# Input_Board.net
KiCad netlist of a schematic drawn in EAGLE
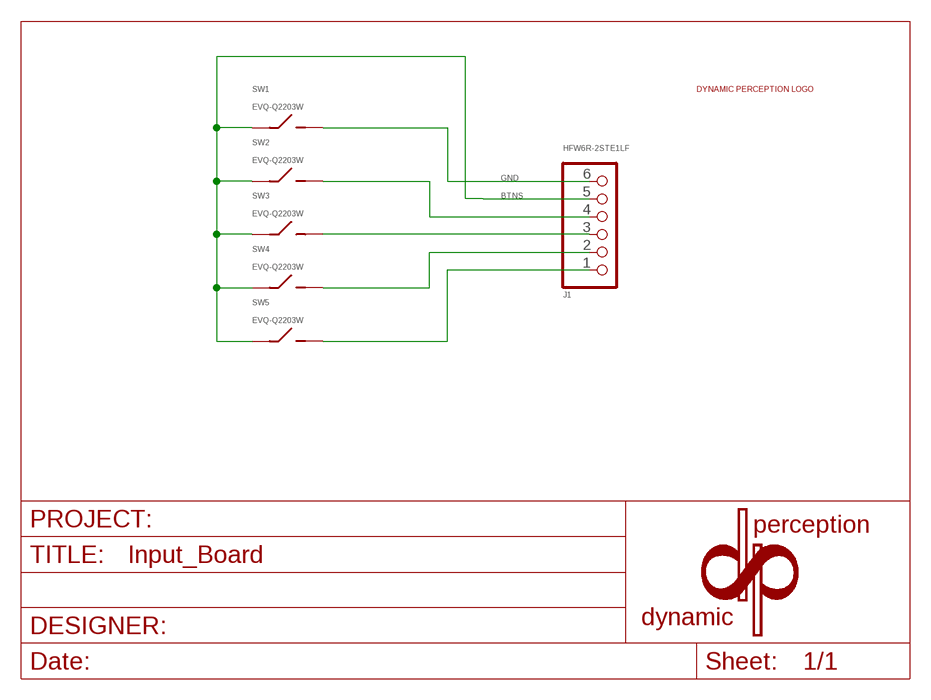
[diagram p0: schematic, sheet 1]

(export (version "E")
  (design (tool "Eeschema 10.0.6"))
  (components
    (comp (ref "FRAME1")
      (value "DYNAMIC_PERCEPTION_FRAMEPCB_INFO")
      (footprint "eagle-import:DYNAMIC_PERCEPTION_FRAME")
      (fields
        (field (name "DNAME") "Parker Dillmann")
        (field (name "PNAME") "D-PAD Input")
        (field (name "REVNUM") "REV 0")
      )
      (libsource (lib "eagle-import") (part "DYNAMIC_PERCEPTION_FRAMEPCB_INFO"))
    )
    (comp (ref "J1")
      (value "HFW6R-2STE1LF")
      (footprint "eagle-import:HFW6R-2STE1LF")
      (libsource (lib "eagle-import") (part "PH_1X06FFC"))
    )
    (comp (ref "LOGO2")
      (value "DYNAMIC_PERCEPTION_LOGOMICRO")
      (footprint "eagle-import:DP_LOGO_MICRO")
      (libsource (lib "eagle-import") (part "DYNAMIC_PERCEPTION_LOGOMICRO"))
    )
    (comp (ref "SW1")
      (value "EVQ-Q2203W")
      (footprint "eagle-import:EVQ-Q2203W")
      (libsource (lib "eagle-import") (part "SPSTEVQ-Q2203W"))
    )
    (comp (ref "SW2")
      (value "EVQ-Q2203W")
      (footprint "eagle-import:EVQ-Q2203W")
      (libsource (lib "eagle-import") (part "SPSTEVQ-Q2203W"))
    )
    (comp (ref "SW3")
      (value "EVQ-Q2203W")
      (footprint "eagle-import:EVQ-Q2203W")
      (libsource (lib "eagle-import") (part "SPSTEVQ-Q2203W"))
    )
    (comp (ref "SW4")
      (value "EVQ-Q2203W")
      (footprint "eagle-import:EVQ-Q2203W")
      (libsource (lib "eagle-import") (part "SPSTEVQ-Q2203W"))
    )
    (comp (ref "SW5")
      (value "EVQ-Q2203W")
      (footprint "eagle-import:EVQ-Q2203W")
      (libsource (lib "eagle-import") (part "SPSTEVQ-Q2203W"))
    )
  )
  (nets
    (net (code "1") (name "/BTNS") (class "Default")
      (node (ref "J1") (pin "5") (pinfunction "5_5") (pintype "passive"))
      (node (ref "SW1") (pin "1") (pinfunction "A_1") (pintype "bidirectional"))
      (node (ref "SW1") (pin "2") (pinfunction "A_2") (pintype "bidirectional"))
      (node (ref "SW2") (pin "1") (pinfunction "A_1") (pintype "bidirectional"))
      (node (ref "SW2") (pin "2") (pinfunction "A_2") (pintype "bidirectional"))
      (node (ref "SW3") (pin "1") (pinfunction "A_1") (pintype "bidirectional"))
      (node (ref "SW3") (pin "2") (pinfunction "A_2") (pintype "bidirectional"))
      (node (ref "SW4") (pin "1") (pinfunction "A_1") (pintype "bidirectional"))
      (node (ref "SW4") (pin "2") (pinfunction "A_2") (pintype "bidirectional"))
      (node (ref "SW5") (pin "1") (pinfunction "A_1") (pintype "bidirectional"))
      (node (ref "SW5") (pin "2") (pinfunction "A_2") (pintype "bidirectional"))
    )
    (net (code "2") (name "/GND") (class "Default")
      (node (ref "J1") (pin "6") (pinfunction "6_6") (pintype "passive"))
      (node (ref "SW1") (pin "3") (pinfunction "B_3") (pintype "bidirectional"))
      (node (ref "SW1") (pin "4") (pinfunction "B_4") (pintype "bidirectional"))
    )
    (net (code "3") (name "Net-(J1-Pad1)") (class "Default")
      (node (ref "J1") (pin "1") (pinfunction "1_1") (pintype "passive"))
      (node (ref "SW5") (pin "3") (pinfunction "B_3") (pintype "bidirectional"))
      (node (ref "SW5") (pin "4") (pinfunction "B_4") (pintype "bidirectional"))
    )
    (net (code "4") (name "Net-(J1-Pad2)") (class "Default")
      (node (ref "J1") (pin "2") (pinfunction "2_2") (pintype "passive"))
      (node (ref "SW4") (pin "3") (pinfunction "B_3") (pintype "bidirectional"))
      (node (ref "SW4") (pin "4") (pinfunction "B_4") (pintype "bidirectional"))
    )
    (net (code "5") (name "Net-(J1-Pad3)") (class "Default")
      (node (ref "J1") (pin "3") (pinfunction "3_3") (pintype "passive"))
      (node (ref "SW3") (pin "3") (pinfunction "B_3") (pintype "bidirectional"))
      (node (ref "SW3") (pin "4") (pinfunction "B_4") (pintype "bidirectional"))
    )
    (net (code "6") (name "Net-(J1-Pad4)") (class "Default")
      (node (ref "J1") (pin "4") (pinfunction "4_4") (pintype "passive"))
      (node (ref "SW2") (pin "3") (pinfunction "B_3") (pintype "bidirectional"))
      (node (ref "SW2") (pin "4") (pinfunction "B_4") (pintype "bidirectional"))
    )
  )
)
